# data_proV1_3.net
KiCad netlist of a schematic drawn in EAGLE
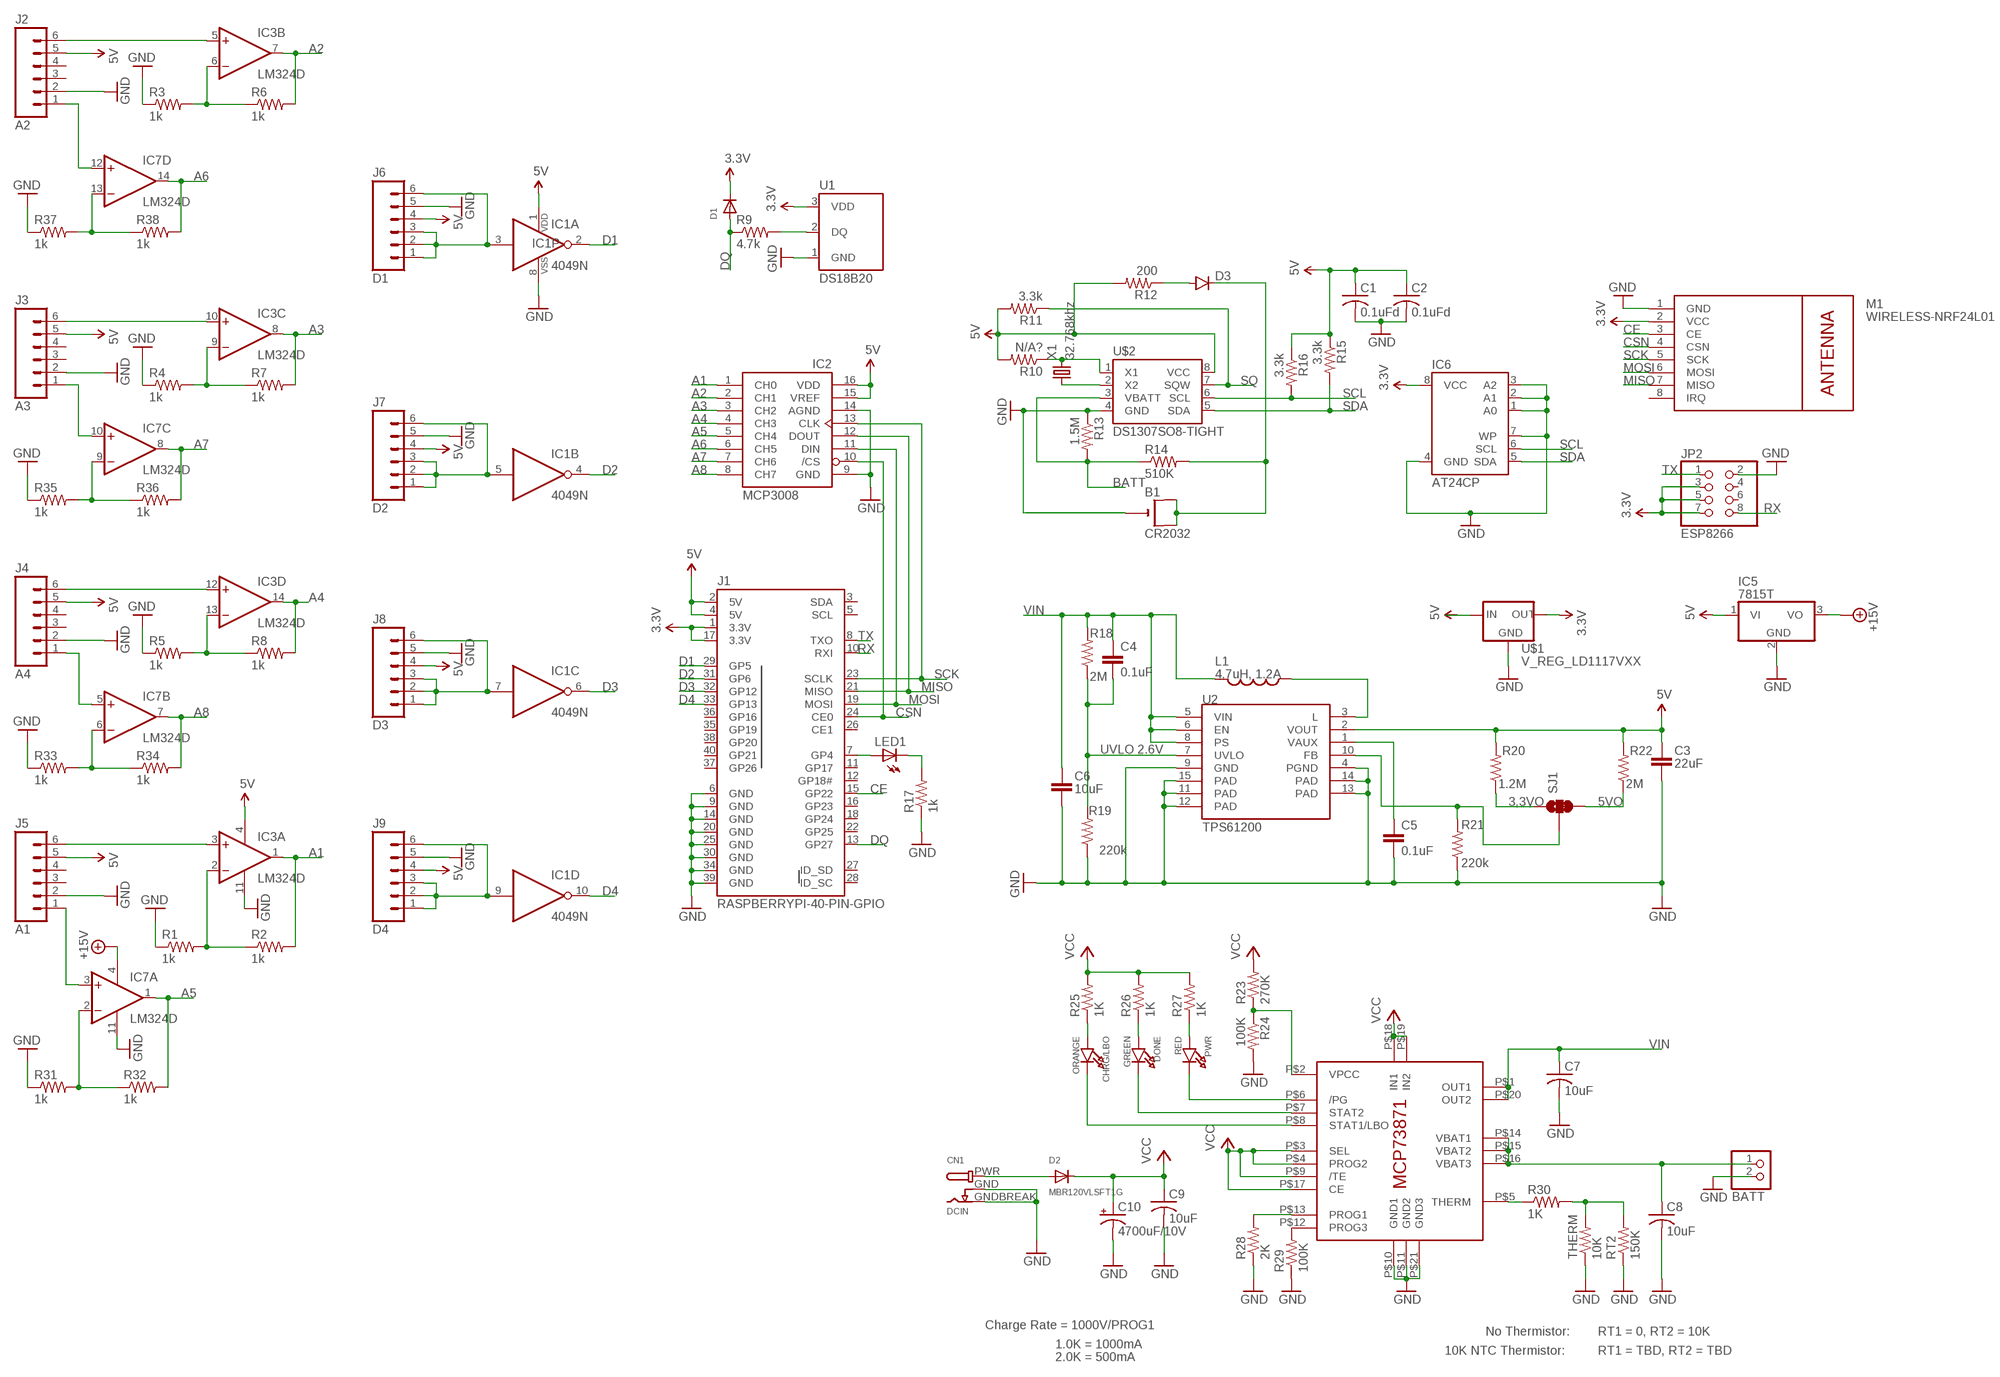
[diagram p0: schematic, sheet 1]

(export (version "E")
  (design (tool "Eeschema 10.0.6"))
  (components
    (comp (ref "B1")
      (value "CR2032")
      (footprint "eagle-import:CR2032-SMD")
      (libsource (lib "eagle-import") (part "CR2032SMT"))
    )
    (comp (ref "BATT")
      (value "JST_2PIN-SMT-RA")
      (footprint "eagle-import:JST-PH-2-SMT-RA")
      (libsource (lib "eagle-import") (part "JST_2PIN-SMT-RA"))
    )
    (comp (ref "C1")
      (value "0.1uFd")
      (footprint "eagle-import:C0805")
      (libsource (lib "eagle-import") (part "resistor_C-USC0805"))
    )
    (comp (ref "C2")
      (value "0.1uFd")
      (footprint "eagle-import:C0805")
      (libsource (lib "eagle-import") (part "resistor_C-USC0805"))
    )
    (comp (ref "C3")
      (value "22uF")
      (footprint "eagle-import:0805")
      (libsource (lib "eagle-import") (part "CAP0805"))
    )
    (comp (ref "C4")
      (value "0.1uF")
      (footprint "eagle-import:0603-CAP")
      (libsource (lib "eagle-import") (part "CAP0603-CAP"))
    )
    (comp (ref "C5")
      (value "0.1uF")
      (footprint "eagle-import:0603-CAP")
      (libsource (lib "eagle-import") (part "CAP0603-CAP"))
    )
    (comp (ref "C6")
      (value "10uF")
      (footprint "eagle-import:1206")
      (libsource (lib "eagle-import") (part "CAP1206"))
    )
    (comp (ref "C7")
      (value "10uF")
      (footprint "eagle-import:C0805K")
      (libsource (lib "eagle-import") (part "C-USC0805K"))
    )
    (comp (ref "C8")
      (value "10uF")
      (footprint "eagle-import:C0805K")
      (libsource (lib "eagle-import") (part "C-USC0805K"))
    )
    (comp (ref "C9")
      (value "10uF")
      (footprint "eagle-import:C0805K")
      (libsource (lib "eagle-import") (part "C-USC0805K"))
    )
    (comp (ref "C10")
      (value "4700uF/10V")
      (footprint "eagle-import:E5-13")
      (libsource (lib "eagle-import") (part "CPOL-USE5-13"))
    )
    (comp (ref "CHRG/LBO")
      (value "ORANGE")
      (footprint "eagle-import:CHIPLED_0805_NOOUTLINE")
      (libsource (lib "eagle-import") (part "LED0805_NOOUTLINE"))
    )
    (comp (ref "CN1")
      (value "DCIN")
      (footprint "eagle-import:DCJACK_2MM_SMT")
      (libsource (lib "eagle-import") (part "DCBARRELSMT"))
    )
    (comp (ref "D1")
      (value "DIODESOD-323F")
      (footprint "eagle-import:SOD-323F")
      (libsource (lib "eagle-import") (part "DIODESOD-323F"))
    )
    (comp (ref "D2")
      (value "MBR120VLSFT1G")
      (footprint "eagle-import:SOD-123")
      (libsource (lib "eagle-import") (part "microbuilder_DIODESOD-123"))
    )
    (comp (ref "D3")
      (value "DIODESMB")
      (footprint "eagle-import:SMB-DIODE")
      (libsource (lib "eagle-import") (part "DIODESMB"))
    )
    (comp (ref "DONE")
      (value "GREEN")
      (footprint "eagle-import:CHIPLED_0805_NOOUTLINE")
      (libsource (lib "eagle-import") (part "LED0805_NOOUTLINE"))
    )
    (comp (ref "IC1")
      (value "4049N")
      (footprint "eagle-import:DIL16")
      (libsource (lib "eagle-import") (part "4049N"))
    )
    (comp (ref "IC2")
      (value "MCP3008")
      (footprint "eagle-import:DIL16")
      (libsource (lib "eagle-import") (part "MCP3008"))
    )
    (comp (ref "IC3")
      (value "LM324D")
      (footprint "eagle-import:SO14")
      (libsource (lib "eagle-import") (part "LM324D"))
    )
    (comp (ref "IC4")
      (value "MCP73871")
      (footprint "eagle-import:QFN20_4MM")
      (libsource (lib "eagle-import") (part "MCP73871"))
    )
    (comp (ref "IC5")
      (value "7815T")
      (footprint "eagle-import:TO220H")
      (libsource (lib "eagle-import") (part "78T15"))
    )
    (comp (ref "IC6")
      (value "AT24CP")
      (footprint "eagle-import:DIL08")
      (fields (field (name "MPN") "AT24C1024BW-SH-B"))
      (libsource (lib "eagle-import") (part "AT24CP"))
    )
    (comp (ref "IC7")
      (value "LM324D")
      (footprint "eagle-import:SO14")
      (libsource (lib "eagle-import") (part "LM324D"))
    )
    (comp (ref "J1")
      (value "RASPBERRYPI-40-PIN-GPIO")
      (footprint "eagle-import:2X20-SHROUDED")
      (libsource (lib "eagle-import") (part "RASPBERRYPI-40-PIN-GPIO"))
    )
    (comp (ref "J2")
      (value "A2")
      (footprint "eagle-import:BTA")
      (libsource (lib "eagle-import") (part "M06VERNIER-ANALOG"))
    )
    (comp (ref "J3")
      (value "A3")
      (footprint "eagle-import:BTA")
      (libsource (lib "eagle-import") (part "M06VERNIER-ANALOG"))
    )
    (comp (ref "J4")
      (value "A4")
      (footprint "eagle-import:BTA")
      (libsource (lib "eagle-import") (part "M06VERNIER-ANALOG"))
    )
    (comp (ref "J5")
      (value "A1")
      (footprint "eagle-import:BTA")
      (libsource (lib "eagle-import") (part "M06VERNIER-ANALOG"))
    )
    (comp (ref "J6")
      (value "D1")
      (footprint "eagle-import:BTD")
      (libsource (lib "eagle-import") (part "M06VERNIER-DIGITAL"))
    )
    (comp (ref "J7")
      (value "D2")
      (footprint "eagle-import:BTD")
      (libsource (lib "eagle-import") (part "M06VERNIER-DIGITAL"))
    )
    (comp (ref "J8")
      (value "D3")
      (footprint "eagle-import:BTD")
      (libsource (lib "eagle-import") (part "M06VERNIER-DIGITAL"))
    )
    (comp (ref "J9")
      (value "D4")
      (footprint "eagle-import:BTD")
      (libsource (lib "eagle-import") (part "M06VERNIER-DIGITAL"))
    )
    (comp (ref "JP2")
      (value "ESP8266")
      (footprint "eagle-import:2X04")
      (libsource (lib "eagle-import") (part "PINHD-2X4"))
    )
    (comp (ref "L1")
      (value "4.7uH, 1.2A")
      (footprint "eagle-import:CDRH2D09")
      (libsource (lib "eagle-import") (part "INDUCTOR."))
    )
    (comp (ref "LED1")
      (value "LEDCHIP-LED0805")
      (footprint "eagle-import:CHIP-LED0805")
      (libsource (lib "eagle-import") (part "LEDCHIP-LED0805"))
    )
    (comp (ref "M1")
      (value "WIRELESS-NRF24L01")
      (footprint "eagle-import:WIRELESS-NRF24L01")
      (libsource (lib "eagle-import") (part "WIRELESS-NRF24L01"))
    )
    (comp (ref "PWR")
      (value "RED")
      (footprint "eagle-import:CHIPLED_0805_NOOUTLINE")
      (libsource (lib "eagle-import") (part "LED0805_NOOUTLINE"))
    )
    (comp (ref "R1")
      (value "1k")
      (footprint "eagle-import:R0805")
      (libsource (lib "eagle-import") (part "resistor_R-US_R0805"))
    )
    (comp (ref "R2")
      (value "1k")
      (footprint "eagle-import:R0805")
      (libsource (lib "eagle-import") (part "resistor_R-US_R0805"))
    )
    (comp (ref "R3")
      (value "1k")
      (footprint "eagle-import:R0805")
      (libsource (lib "eagle-import") (part "resistor_R-US_R0805"))
    )
    (comp (ref "R4")
      (value "1k")
      (footprint "eagle-import:R0805")
      (libsource (lib "eagle-import") (part "resistor_R-US_R0805"))
    )
    (comp (ref "R5")
      (value "1k")
      (footprint "eagle-import:R0805")
      (libsource (lib "eagle-import") (part "resistor_R-US_R0805"))
    )
    (comp (ref "R6")
      (value "1k")
      (footprint "eagle-import:R0805")
      (libsource (lib "eagle-import") (part "resistor_R-US_R0805"))
    )
    (comp (ref "R7")
      (value "1k")
      (footprint "eagle-import:R0805")
      (libsource (lib "eagle-import") (part "resistor_R-US_R0805"))
    )
    (comp (ref "R8")
      (value "1k")
      (footprint "eagle-import:R0805")
      (libsource (lib "eagle-import") (part "resistor_R-US_R0805"))
    )
    (comp (ref "R9")
      (value "4.7k")
      (footprint "eagle-import:R0805")
      (libsource (lib "eagle-import") (part "resistor_R-US_R0805"))
    )
    (comp (ref "R10")
      (value "N/A?")
      (footprint "eagle-import:R0805")
      (libsource (lib "eagle-import") (part "R-US_R0805"))
    )
    (comp (ref "R11")
      (value "3.3k")
      (footprint "eagle-import:R0805")
      (libsource (lib "eagle-import") (part "R-US_R0805"))
    )
    (comp (ref "R12")
      (value "200")
      (footprint "eagle-import:R0805")
      (libsource (lib "eagle-import") (part "R-US_R0805"))
    )
    (comp (ref "R13")
      (value "1.5M")
      (footprint "eagle-import:R0805")
      (libsource (lib "eagle-import") (part "R-US_R0805"))
    )
    (comp (ref "R14")
      (value "510K")
      (footprint "eagle-import:R0805")
      (libsource (lib "eagle-import") (part "R-US_R0805"))
    )
    (comp (ref "R15")
      (value "3.3k")
      (footprint "eagle-import:R0805")
      (libsource (lib "eagle-import") (part "R-US_R0805"))
    )
    (comp (ref "R16")
      (value "3.3k")
      (footprint "eagle-import:R0805")
      (libsource (lib "eagle-import") (part "R-US_R0805"))
    )
    (comp (ref "R17")
      (value "1k")
      (footprint "eagle-import:R0805")
      (libsource (lib "eagle-import") (part "R-US_R0805"))
    )
    (comp (ref "R18")
      (value "2M")
      (footprint "eagle-import:0603-RES")
      (libsource (lib "eagle-import") (part "RESISTOR0603-RES"))
    )
    (comp (ref "R19")
      (value "220k")
      (footprint "eagle-import:0603-RES")
      (libsource (lib "eagle-import") (part "RESISTOR0603-RES"))
    )
    (comp (ref "R20")
      (value "1.2M")
      (footprint "eagle-import:0603-RES")
      (libsource (lib "eagle-import") (part "RESISTOR0603-RES"))
    )
    (comp (ref "R21")
      (value "220k")
      (footprint "eagle-import:0603-RES")
      (libsource (lib "eagle-import") (part "RESISTOR0603-RES"))
    )
    (comp (ref "R22")
      (value "2M")
      (footprint "eagle-import:0603-RES")
      (libsource (lib "eagle-import") (part "RESISTOR0603-RES"))
    )
    (comp (ref "R23")
      (value "270K")
      (footprint "eagle-import:R0805")
      (libsource (lib "eagle-import") (part "R-US_R0805"))
    )
    (comp (ref "R24")
      (value "100K")
      (footprint "eagle-import:R0805")
      (libsource (lib "eagle-import") (part "R-US_R0805"))
    )
    (comp (ref "R25")
      (value "1K")
      (footprint "eagle-import:R0805")
      (libsource (lib "eagle-import") (part "R-US_R0805"))
    )
    (comp (ref "R26")
      (value "1K")
      (footprint "eagle-import:R0805")
      (libsource (lib "eagle-import") (part "R-US_R0805"))
    )
    (comp (ref "R27")
      (value "1K")
      (footprint "eagle-import:R0805")
      (libsource (lib "eagle-import") (part "R-US_R0805"))
    )
    (comp (ref "R28")
      (value "2K")
      (footprint "eagle-import:0805-THM")
      (libsource (lib "eagle-import") (part "R-US_FLIPFLOP"))
    )
    (comp (ref "R29")
      (value "100K")
      (footprint "eagle-import:R0805")
      (libsource (lib "eagle-import") (part "R-US_R0805"))
    )
    (comp (ref "R30")
      (value "1K")
      (footprint "eagle-import:M0805")
      (libsource (lib "eagle-import") (part "R-US_M0805"))
    )
    (comp (ref "R31")
      (value "1k")
      (footprint "eagle-import:R0805")
      (libsource (lib "eagle-import") (part "resistor_R-US_R0805"))
    )
    (comp (ref "R32")
      (value "1k")
      (footprint "eagle-import:R0805")
      (libsource (lib "eagle-import") (part "resistor_R-US_R0805"))
    )
    (comp (ref "R33")
      (value "1k")
      (footprint "eagle-import:R0805")
      (libsource (lib "eagle-import") (part "resistor_R-US_R0805"))
    )
    (comp (ref "R34")
      (value "1k")
      (footprint "eagle-import:R0805")
      (libsource (lib "eagle-import") (part "resistor_R-US_R0805"))
    )
    (comp (ref "R35")
      (value "1k")
      (footprint "eagle-import:R0805")
      (libsource (lib "eagle-import") (part "resistor_R-US_R0805"))
    )
    (comp (ref "R36")
      (value "1k")
      (footprint "eagle-import:R0805")
      (libsource (lib "eagle-import") (part "resistor_R-US_R0805"))
    )
    (comp (ref "R37")
      (value "1k")
      (footprint "eagle-import:R0805")
      (libsource (lib "eagle-import") (part "resistor_R-US_R0805"))
    )
    (comp (ref "R38")
      (value "1k")
      (footprint "eagle-import:R0805")
      (libsource (lib "eagle-import") (part "resistor_R-US_R0805"))
    )
    (comp (ref "RT2")
      (value "150K")
      (footprint "eagle-import:M0805")
      (libsource (lib "eagle-import") (part "R-US_M0805"))
    )
    (comp (ref "SJ1")
      (value "SOLDERJUMPER_2WAYPASTE2&3")
      (footprint "eagle-import:SJ_3_PASTE2&3")
      (libsource (lib "eagle-import") (part "SOLDERJUMPER_2WAYPASTE2&3"))
    )
    (comp (ref "THERM")
      (value "10K")
      (footprint "eagle-import:0805-THM")
      (libsource (lib "eagle-import") (part "R-US_FLIPFLOP"))
    )
    (comp (ref "U$1")
      (value "V_REG_LD1117VXX")
      (footprint "eagle-import:78XXL")
      (libsource (lib "eagle-import") (part "V_REG_LD1117VXX"))
    )
    (comp (ref "U$2")
      (value "DS1307SO8-TIGHT")
      (footprint "eagle-import:SO08-TIGHT")
      (libsource (lib "eagle-import") (part "DS1307SO8-TIGHT"))
    )
    (comp (ref "U1")
      (value "DS18B20")
      (footprint "eagle-import:TO-92-AMMO")
      (libsource (lib "eagle-import") (part "DS18B20"))
    )
    (comp (ref "U2")
      (value "TPS61200")
      (footprint "eagle-import:QFN-10_PAD")
      (libsource (lib "eagle-import") (part "TPS61200"))
    )
    (comp (ref "X1")
      (value "32.768khz")
      (footprint "eagle-import:TC38H")
      (libsource (lib "eagle-import") (part "CRYSTALTC38H"))
    )
  )
  (nets
    (net (code "1") (name "+15V") (class "Default")
      (node (ref "IC5") (pin "3") (pinfunction "VO_3") (pintype "passive"))
      (node (ref "IC7") (pin "4") (pinfunction "V+_4") (pintype "power_in"))
    )
    (net (code "2") (name "/3.3VO") (class "Default")
      (node (ref "R20") (pin "1") (pinfunction "1_1") (pintype "passive"))
      (node (ref "SJ1") (pin "1") (pinfunction "1_1") (pintype "passive"))
    )
    (net (code "3") (name "/5VO") (class "Default")
      (node (ref "R22") (pin "1") (pinfunction "1_1") (pintype "passive"))
      (node (ref "SJ1") (pin "3") (pinfunction "3_3") (pintype "passive"))
    )
    (net (code "4") (name "/A1") (class "Default")
      (node (ref "IC2") (pin "1") (pinfunction "CH0_1") (pintype "input"))
      (node (ref "IC3") (pin "1") (pinfunction "OUT_1") (pintype "output"))
      (node (ref "R2") (pin "2") (pinfunction "2_2") (pintype "passive"))
    )
    (net (code "5") (name "/A2") (class "Default")
      (node (ref "IC2") (pin "2") (pinfunction "CH1_2") (pintype "input"))
      (node (ref "IC3") (pin "7") (pinfunction "OUT_7") (pintype "output"))
      (node (ref "R6") (pin "2") (pinfunction "2_2") (pintype "passive"))
    )
    (net (code "6") (name "/A3") (class "Default")
      (node (ref "IC2") (pin "3") (pinfunction "CH2_3") (pintype "input"))
      (node (ref "IC3") (pin "8") (pinfunction "OUT_8") (pintype "output"))
      (node (ref "R7") (pin "2") (pinfunction "2_2") (pintype "passive"))
    )
    (net (code "7") (name "/A4") (class "Default")
      (node (ref "IC2") (pin "4") (pinfunction "CH3_4") (pintype "input"))
      (node (ref "IC3") (pin "14") (pinfunction "OUT_14") (pintype "output"))
      (node (ref "R8") (pin "2") (pinfunction "2_2") (pintype "passive"))
    )
    (net (code "8") (name "/A5") (class "Default")
      (node (ref "IC2") (pin "5") (pinfunction "CH4_5") (pintype "input"))
      (node (ref "IC7") (pin "1") (pinfunction "OUT_1") (pintype "output"))
      (node (ref "R32") (pin "2") (pinfunction "2_2") (pintype "passive"))
    )
    (net (code "9") (name "/A6") (class "Default")
      (node (ref "IC2") (pin "6") (pinfunction "CH5_6") (pintype "input"))
      (node (ref "IC7") (pin "14") (pinfunction "OUT_14") (pintype "output"))
      (node (ref "R38") (pin "2") (pinfunction "2_2") (pintype "passive"))
    )
    (net (code "10") (name "/A7") (class "Default")
      (node (ref "IC2") (pin "7") (pinfunction "CH6_7") (pintype "input"))
      (node (ref "IC7") (pin "8") (pinfunction "OUT_8") (pintype "output"))
      (node (ref "R36") (pin "2") (pinfunction "2_2") (pintype "passive"))
    )
    (net (code "11") (name "/A8") (class "Default")
      (node (ref "IC2") (pin "8") (pinfunction "CH7_8") (pintype "input"))
      (node (ref "IC7") (pin "7") (pinfunction "OUT_7") (pintype "output"))
      (node (ref "R34") (pin "2") (pinfunction "2_2") (pintype "passive"))
    )
    (net (code "12") (name "/BATT") (class "Default")
      (node (ref "R13") (pin "2") (pinfunction "2_2") (pintype "passive"))
      (node (ref "R14") (pin "1") (pinfunction "1_1") (pintype "passive"))
      (node (ref "U$2") (pin "3") (pinfunction "VBATT_3") (pintype "bidirectional"))
    )
    (net (code "13") (name "/CE") (class "Default")
      (node (ref "J1") (pin "15") (pinfunction "GP22_15") (pintype "bidirectional"))
      (node (ref "M1") (pin "3") (pinfunction "CE_3") (pintype "bidirectional"))
    )
    (net (code "14") (name "/CSN") (class "Default")
      (node (ref "IC2") (pin "10") (pinfunction "/CS_10") (pintype "input"))
      (node (ref "J1") (pin "24") (pinfunction "CE0_24") (pintype "output"))
      (node (ref "M1") (pin "4") (pinfunction "CSN_4") (pintype "bidirectional"))
    )
    (net (code "15") (name "/D1") (class "Default")
      (node (ref "IC1") (pin "2") (pinfunction "O_2") (pintype "output"))
      (node (ref "J1") (pin "29") (pinfunction "GP5_29") (pintype "bidirectional"))
    )
    (net (code "16") (name "/D2") (class "Default")
      (node (ref "IC1") (pin "4") (pinfunction "O_4") (pintype "output"))
      (node (ref "J1") (pin "31") (pinfunction "GP6_31") (pintype "bidirectional"))
    )
    (net (code "17") (name "/D3") (class "Default")
      (node (ref "IC1") (pin "6") (pinfunction "O_6") (pintype "output"))
      (node (ref "J1") (pin "32") (pinfunction "GP12_32") (pintype "bidirectional"))
    )
    (net (code "18") (name "/D4") (class "Default")
      (node (ref "IC1") (pin "10") (pinfunction "O_10") (pintype "output"))
      (node (ref "J1") (pin "33") (pinfunction "GP13_33") (pintype "bidirectional"))
    )
    (net (code "19") (name "/DQ") (class "Default")
      (node (ref "D1") (pin "A") (pinfunction "A_A") (pintype "passive"))
      (node (ref "J1") (pin "13") (pinfunction "GP27_13") (pintype "bidirectional"))
      (node (ref "R9") (pin "1") (pinfunction "1_1") (pintype "passive"))
    )
    (net (code "20") (name "/MISO") (class "Default")
      (node (ref "IC2") (pin "12") (pinfunction "DOUT_12") (pintype "output"))
      (node (ref "J1") (pin "21") (pinfunction "MISO_21") (pintype "input"))
      (node (ref "M1") (pin "7") (pinfunction "MISO_7") (pintype "bidirectional"))
    )
    (net (code "21") (name "/MOSI") (class "Default")
      (node (ref "IC2") (pin "11") (pinfunction "DIN_11") (pintype "input"))
      (node (ref "J1") (pin "19") (pinfunction "MOSI_19") (pintype "output"))
      (node (ref "M1") (pin "6") (pinfunction "MOSI_6") (pintype "bidirectional"))
    )
    (net (code "22") (name "/RX") (class "Default")
      (node (ref "J1") (pin "10") (pinfunction "RXI_10") (pintype "input"))
      (node (ref "JP2") (pin "8") (pinfunction "8_8") (pintype "passive"))
    )
    (net (code "23") (name "/SCK") (class "Default")
      (node (ref "IC2") (pin "13") (pinfunction "CLK_13") (pintype "input"))
      (node (ref "J1") (pin "23") (pinfunction "SCLK_23") (pintype "output"))
      (node (ref "M1") (pin "5") (pinfunction "SCK_5") (pintype "bidirectional"))
    )
    (net (code "24") (name "/SCL") (class "Default")
      (node (ref "IC6") (pin "6") (pinfunction "SCL_6") (pintype "bidirectional"))
      (node (ref "R16") (pin "2") (pinfunction "2_2") (pintype "passive"))
      (node (ref "U$2") (pin "6") (pinfunction "SCL_6") (pintype "bidirectional"))
    )
    (net (code "25") (name "/SDA") (class "Default")
      (node (ref "IC6") (pin "5") (pinfunction "SDA_5") (pintype "bidirectional"))
      (node (ref "R15") (pin "2") (pinfunction "2_2") (pintype "passive"))
      (node (ref "U$2") (pin "5") (pinfunction "SDA_5") (pintype "bidirectional"))
    )
    (net (code "26") (name "/SQ") (class "Default")
      (node (ref "R11") (pin "1") (pinfunction "1_1") (pintype "passive"))
      (node (ref "U$2") (pin "7") (pinfunction "SQW_7") (pintype "bidirectional"))
    )
    (net (code "27") (name "/TX") (class "Default")
      (node (ref "J1") (pin "8") (pinfunction "TXO_8") (pintype "output"))
      (node (ref "JP2") (pin "1") (pinfunction "1_1") (pintype "passive"))
    )
    (net (code "28") (name "/VIN") (class "Default")
      (node (ref "C4") (pin "1") (pinfunction "1_1") (pintype "passive"))
      (node (ref "C6") (pin "1") (pinfunction "1_1") (pintype "passive"))
      (node (ref "C7") (pin "1") (pinfunction "1_1") (pintype "passive"))
      (node (ref "IC4") (pin "P$1") (pinfunction "OUT1_P$1") (pintype "output"))
      (node (ref "IC4") (pin "P$20") (pinfunction "OUT2_P$20") (pintype "output"))
      (node (ref "L1") (pin "P$2") (pinfunction "2_P$2") (pintype "passive"))
      (node (ref "R18") (pin "2") (pinfunction "2_2") (pintype "passive"))
      (node (ref "U2") (pin "5") (pinfunction "VIN_5") (pintype "power_in"))
      (node (ref "U2") (pin "6") (pinfunction "EN_6") (pintype "input"))
      (node (ref "U2") (pin "8") (pinfunction "PS_8") (pintype "input"))
    )
    (net (code "29") (name "3.3V") (class "Default")
      (node (ref "D1") (pin "C") (pinfunction "C_C") (pintype "passive"))
      (node (ref "IC6") (pin "8") (pinfunction "VCC_8") (pintype "power_in"))
      (node (ref "J1") (pin "1") (pinfunction "3.3V_1") (pintype "power_in"))
      (node (ref "J1") (pin "17") (pinfunction "3.3V_17") (pintype "power_in"))
      (node (ref "JP2") (pin "3") (pinfunction "3_3") (pintype "passive"))
      (node (ref "JP2") (pin "5") (pinfunction "5_5") (pintype "passive"))
      (node (ref "JP2") (pin "7") (pinfunction "7_7") (pintype "passive"))
      (node (ref "M1") (pin "2") (pinfunction "VCC_2") (pintype "power_in"))
      (node (ref "U$1") (pin "GND") (pinfunction "OUT_GND") (pintype "passive"))
      (node (ref "U1") (pin "3") (pinfunction "VDD_3") (pintype "power_in"))
    )
    (net (code "30") (name "5V") (class "Default")
      (node (ref "C1") (pin "1") (pinfunction "1_1") (pintype "passive"))
      (node (ref "C2") (pin "1") (pinfunction "1_1") (pintype "passive"))
      (node (ref "C3") (pin "1") (pinfunction "1_1") (pintype "passive"))
      (node (ref "IC1") (pin "1") (pinfunction "VDD_1") (pintype "power_in"))
      (node (ref "IC2") (pin "15") (pinfunction "VREF_15") (pintype "input"))
      (node (ref "IC2") (pin "16") (pinfunction "VDD_16") (pintype "power_in"))
      (node (ref "IC3") (pin "4") (pinfunction "V+_4") (pintype "power_in"))
      (node (ref "IC5") (pin "1") (pinfunction "VI_1") (pintype "input"))
      (node (ref "J1") (pin "2") (pinfunction "5V_2") (pintype "power_in"))
      (node (ref "J1") (pin "4") (pinfunction "5V_4") (pintype "power_in"))
      (node (ref "J2") (pin "5") (pinfunction "5_5") (pintype "passive"))
      (node (ref "J3") (pin "5") (pinfunction "5_5") (pintype "passive"))
      (node (ref "J4") (pin "5") (pinfunction "5_5") (pintype "passive"))
      (node (ref "J5") (pin "5") (pinfunction "5_5") (pintype "passive"))
      (node (ref "J6") (pin "4") (pinfunction "4_4") (pintype "passive"))
      (node (ref "J7") (pin "4") (pinfunction "4_4") (pintype "passive"))
      (node (ref "J8") (pin "4") (pinfunction "4_4") (pintype "passive"))
      (node (ref "J9") (pin "4") (pinfunction "4_4") (pintype "passive"))
      (node (ref "R10") (pin "2") (pinfunction "2_2") (pintype "passive"))
      (node (ref "R11") (pin "2") (pinfunction "2_2") (pintype "passive"))
      (node (ref "R12") (pin "2") (pinfunction "2_2") (pintype "passive"))
      (node (ref "R15") (pin "1") (pinfunction "1_1") (pintype "passive"))
      (node (ref "R16") (pin "1") (pinfunction "1_1") (pintype "passive"))
      (node (ref "R20") (pin "2") (pinfunction "2_2") (pintype "passive"))
      (node (ref "R22") (pin "2") (pinfunction "2_2") (pintype "passive"))
      (node (ref "U$1") (pin "OUT") (pinfunction "IN_OUT") (pintype "input"))
      (node (ref "U$2") (pin "8") (pinfunction "VCC_8") (pintype "bidirectional"))
      (node (ref "U2") (pin "2") (pinfunction "VOUT_2") (pintype "passive"))
    )
    (net (code "31") (name "GND") (class "Default")
      (node (ref "B1") (pin "-") (pinfunction "-_-") (pintype "passive"))
      (node (ref "BATT") (pin "2") (pinfunction "1_2") (pintype "passive"))
      (node (ref "C1") (pin "2") (pinfunction "2_2") (pintype "passive"))
      (node (ref "C10") (pin "-") (pinfunction "-_-") (pintype "passive"))
      (node (ref "C2") (pin "2") (pinfunction "2_2") (pintype "passive"))
      (node (ref "C3") (pin "2") (pinfunction "2_2") (pintype "passive"))
      (node (ref "C5") (pin "2") (pinfunction "2_2") (pintype "passive"))
      (node (ref "C6") (pin "2") (pinfunction "2_2") (pintype "passive"))
      (node (ref "C7") (pin "2") (pinfunction "2_2") (pintype "passive"))
      (node (ref "C8") (pin "2") (pinfunction "2_2") (pintype "passive"))
      (node (ref "C9") (pin "2") (pinfunction "2_2") (pintype "passive"))
      (node (ref "CN1") (pin "GND") (pinfunction "GNDBREAK_GND") (pintype "power_in"))
      (node (ref "CN1") (pin "GNDBREAK") (pinfunction "GND_GNDBREAK") (pintype "power_in"))
      (node (ref "IC1") (pin "8") (pinfunction "VSS_8") (pintype "power_in"))
      (node (ref "IC2") (pin "14") (pinfunction "AGND_14") (pintype "power_in"))
      (node (ref "IC2") (pin "9") (pinfunction "GND_9") (pintype "power_in"))
      (node (ref "IC3") (pin "11") (pinfunction "V-_11") (pintype "power_in"))
      (node (ref "IC4") (pin "P$10") (pinfunction "GND1_P$10") (pintype "power_in"))
      (node (ref "IC4") (pin "P$11") (pinfunction "GND2_P$11") (pintype "power_in"))
      (node (ref "IC4") (pin "P$21") (pinfunction "GND3_P$21") (pintype "power_in"))
      (node (ref "IC5") (pin "2") (pinfunction "GND_2") (pintype "passive"))
      (node (ref "IC6") (pin "1") (pinfunction "A0_1") (pintype "input"))
      (node (ref "IC6") (pin "2") (pinfunction "A1_2") (pintype "input"))
      (node (ref "IC6") (pin "3") (pinfunction "A2_3") (pintype "input"))
      (node (ref "IC6") (pin "4") (pinfunction "GND_4") (pintype "power_in"))
      (node (ref "IC6") (pin "7") (pinfunction "WP_7") (pintype "input"))
      (node (ref "IC7") (pin "11") (pinfunction "V-_11") (pintype "power_in"))
      (node (ref "J1") (pin "14") (pinfunction "GND_14") (pintype "power_in"))
      (node (ref "J1") (pin "20") (pinfunction "GND_20") (pintype "power_in"))
      (node (ref "J1") (pin "25") (pinfunction "GND_25") (pintype "power_in"))
      (node (ref "J1") (pin "30") (pinfunction "GND_30") (pintype "power_in"))
      (node (ref "J1") (pin "34") (pinfunction "GND_34") (pintype "power_in"))
      (node (ref "J1") (pin "39") (pinfunction "GND_39") (pintype "power_in"))
      (node (ref "J1") (pin "6") (pinfunction "GND_6") (pintype "power_in"))
      (node (ref "J1") (pin "9") (pinfunction "GND_9") (pintype "power_in"))
      (node (ref "J2") (pin "2") (pinfunction "2_2") (pintype "passive"))
      (node (ref "J3") (pin "2") (pinfunction "2_2") (pintype "passive"))
      (node (ref "J4") (pin "2") (pinfunction "2_2") (pintype "passive"))
      (node (ref "J5") (pin "2") (pinfunction "2_2") (pintype "passive"))
      (node (ref "J6") (pin "5") (pinfunction "5_5") (pintype "passive"))
      (node (ref "J7") (pin "5") (pinfunction "5_5") (pintype "passive"))
      (node (ref "J8") (pin "5") (pinfunction "5_5") (pintype "passive"))
      (node (ref "J9") (pin "5") (pinfunction "5_5") (pintype "passive"))
      (node (ref "JP2") (pin "2") (pinfunction "2_2") (pintype "passive"))
      (node (ref "M1") (pin "1") (pinfunction "GND_1") (pintype "power_in"))
      (node (ref "R1") (pin "1") (pinfunction "1_1") (pintype "passive"))
      (node (ref "R13") (pin "1") (pinfunction "1_1") (pintype "passive"))
      (node (ref "R17") (pin "1") (pinfunction "1_1") (pintype "passive"))
      (node (ref "R19") (pin "1") (pinfunction "1_1") (pintype "passive"))
      (node (ref "R21") (pin "1") (pinfunction "1_1") (pintype "passive"))
      (node (ref "R24") (pin "2") (pinfunction "2_2") (pintype "passive"))
      (node (ref "R28") (pin "1") (pinfunction "1_1") (pintype "passive"))
      (node (ref "R29") (pin "1") (pinfunction "1_1") (pintype "passive"))
      (node (ref "R3") (pin "1") (pinfunction "1_1") (pintype "passive"))
      (node (ref "R31") (pin "1") (pinfunction "1_1") (pintype "passive"))
      (node (ref "R33") (pin "1") (pinfunction "1_1") (pintype "passive"))
      (node (ref "R35") (pin "1") (pinfunction "1_1") (pintype "passive"))
      (node (ref "R37") (pin "1") (pinfunction "1_1") (pintype "passive"))
      (node (ref "R4") (pin "1") (pinfunction "1_1") (pintype "passive"))
      (node (ref "R5") (pin "1") (pinfunction "1_1") (pintype "passive"))
      (node (ref "RT2") (pin "1") (pinfunction "1_1") (pintype "passive"))
      (node (ref "THERM") (pin "1") (pinfunction "1_1") (pintype "passive"))
      (node (ref "U$1") (pin "IN") (pinfunction "GND_IN") (pintype "input"))
      (node (ref "U$2") (pin "4") (pinfunction "GND_4") (pintype "bidirectional"))
      (node (ref "U1") (pin "1") (pinfunction "GND_1") (pintype "power_in"))
      (node (ref "U2") (pin "11") (pinfunction "PAD_11") (pintype "power_in"))
      (node (ref "U2") (pin "12") (pinfunction "PAD_12") (pintype "power_in"))
      (node (ref "U2") (pin "13") (pinfunction "PAD_13") (pintype "power_in"))
      (node (ref "U2") (pin "14") (pinfunction "PAD_14") (pintype "power_in"))
      (node (ref "U2") (pin "15") (pinfunction "PAD_15") (pintype "power_in"))
      (node (ref "U2") (pin "4") (pinfunction "PGND_4") (pintype "power_in"))
      (node (ref "U2") (pin "9") (pinfunction "GND_9") (pintype "power_in"))
    )
    (net (code "32") (name "Net-(B1-+)") (class "Default")
      (node (ref "B1") (pin "+$1") (pinfunction "+_+$1") (pintype "passive"))
      (node (ref "B1") (pin "+$2") (pinfunction "+1_+$2") (pintype "passive"))
      (node (ref "D3") (pin "C") (pinfunction "C_C") (pintype "passive"))
      (node (ref "R14") (pin "2") (pinfunction "2_2") (pintype "passive"))
    )
    (net (code "33") (name "Net-(BATT-2)") (class "Default")
      (node (ref "BATT") (pin "1") (pinfunction "2_1") (pintype "passive"))
      (node (ref "C8") (pin "1") (pinfunction "1_1") (pintype "passive"))
      (node (ref "IC4") (pin "P$14") (pinfunction "VBAT1_P$14") (pintype "output"))
      (node (ref "IC4") (pin "P$15") (pinfunction "VBAT2_P$15") (pintype "output"))
      (node (ref "IC4") (pin "P$16") (pinfunction "VBAT3_P$16") (pintype "output"))
    )
    (net (code "34") (name "Net-(CHRG/LBO-PadA)") (class "Default")
      (node (ref "CHRG/LBO") (pin "A") (pinfunction "A_A") (pintype "passive"))
      (node (ref "R25") (pin "1") (pinfunction "1_1") (pintype "passive"))
    )
    (net (code "35") (name "Net-(CN1-PadPWR)") (class "Default")
      (node (ref "CN1") (pin "PWR") (pinfunction "PWR_PWR") (pintype "power_in"))
      (node (ref "D2") (pin "A") (pinfunction "A_A") (pintype "passive"))
    )
    (net (code "36") (name "Net-(D3-PadA)") (class "Default")
      (node (ref "D3") (pin "A") (pinfunction "A_A") (pintype "passive"))
      (node (ref "R12") (pin "1") (pinfunction "1_1") (pintype "passive"))
    )
    (net (code "37") (name "Net-(DONE-PadA)") (class "Default")
      (node (ref "DONE") (pin "A") (pinfunction "A_A") (pintype "passive"))
      (node (ref "R26") (pin "1") (pinfunction "1_1") (pintype "passive"))
    )
    (net (code "38") (name "Net-(IC1A-I)") (class "Default")
      (node (ref "IC1") (pin "3") (pinfunction "I_3") (pintype "input"))
      (node (ref "J6") (pin "1") (pinfunction "1_1") (pintype "passive"))
      (node (ref "J6") (pin "2") (pinfunction "2_2") (pintype "passive"))
      (node (ref "J6") (pin "3") (pinfunction "3_3") (pintype "passive"))
      (node (ref "J6") (pin "6") (pinfunction "6_6") (pintype "passive"))
    )
    (net (code "39") (name "Net-(IC1B-I)") (class "Default")
      (node (ref "IC1") (pin "5") (pinfunction "I_5") (pintype "input"))
      (node (ref "J7") (pin "1") (pinfunction "1_1") (pintype "passive"))
      (node (ref "J7") (pin "2") (pinfunction "2_2") (pintype "passive"))
      (node (ref "J7") (pin "3") (pinfunction "3_3") (pintype "passive"))
      (node (ref "J7") (pin "6") (pinfunction "6_6") (pintype "passive"))
    )
    (net (code "40") (name "Net-(IC1C-I)") (class "Default")
      (node (ref "IC1") (pin "7") (pinfunction "I_7") (pintype "input"))
      (node (ref "J8") (pin "1") (pinfunction "1_1") (pintype "passive"))
      (node (ref "J8") (pin "2") (pinfunction "2_2") (pintype "passive"))
      (node (ref "J8") (pin "3") (pinfunction "3_3") (pintype "passive"))
      (node (ref "J8") (pin "6") (pinfunction "6_6") (pintype "passive"))
    )
    (net (code "41") (name "Net-(IC1D-I)") (class "Default")
      (node (ref "IC1") (pin "9") (pinfunction "I_9") (pintype "input"))
      (node (ref "J9") (pin "1") (pinfunction "1_1") (pintype "passive"))
      (node (ref "J9") (pin "2") (pinfunction "2_2") (pintype "passive"))
      (node (ref "J9") (pin "3") (pinfunction "3_3") (pintype "passive"))
      (node (ref "J9") (pin "6") (pinfunction "6_6") (pintype "passive"))
    )
    (net (code "42") (name "Net-(IC3A-+IN)") (class "Default")
      (node (ref "IC3") (pin "3") (pinfunction "+IN_3") (pintype "input"))
      (node (ref "J5") (pin "6") (pinfunction "6_6") (pintype "passive"))
    )
    (net (code "43") (name "Net-(IC3A--IN)") (class "Default")
      (node (ref "IC3") (pin "2") (pinfunction "-IN_2") (pintype "input"))
      (node (ref "R1") (pin "2") (pinfunction "2_2") (pintype "passive"))
      (node (ref "R2") (pin "1") (pinfunction "1_1") (pintype "passive"))
    )
    (net (code "44") (name "Net-(IC3B-+IN)") (class "Default")
      (node (ref "IC3") (pin "5") (pinfunction "+IN_5") (pintype "input"))
      (node (ref "J2") (pin "6") (pinfunction "6_6") (pintype "passive"))
    )
    (net (code "45") (name "Net-(IC3B--IN)") (class "Default")
      (node (ref "IC3") (pin "6") (pinfunction "-IN_6") (pintype "input"))
      (node (ref "R3") (pin "2") (pinfunction "2_2") (pintype "passive"))
      (node (ref "R6") (pin "1") (pinfunction "1_1") (pintype "passive"))
    )
    (net (code "46") (name "Net-(IC3C-+IN)") (class "Default")
      (node (ref "IC3") (pin "10") (pinfunction "+IN_10") (pintype "input"))
      (node (ref "J3") (pin "6") (pinfunction "6_6") (pintype "passive"))
    )
    (net (code "47") (name "Net-(IC3C--IN)") (class "Default")
      (node (ref "IC3") (pin "9") (pinfunction "-IN_9") (pintype "input"))
      (node (ref "R4") (pin "2") (pinfunction "2_2") (pintype "passive"))
      (node (ref "R7") (pin "1") (pinfunction "1_1") (pintype "passive"))
    )
    (net (code "48") (name "Net-(IC3D-+IN)") (class "Default")
      (node (ref "IC3") (pin "12") (pinfunction "+IN_12") (pintype "input"))
      (node (ref "J4") (pin "6") (pinfunction "6_6") (pintype "passive"))
    )
    (net (code "49") (name "Net-(IC3D--IN)") (class "Default")
      (node (ref "IC3") (pin "13") (pinfunction "-IN_13") (pintype "input"))
      (node (ref "R5") (pin "2") (pinfunction "2_2") (pintype "passive"))
      (node (ref "R8") (pin "1") (pinfunction "1_1") (pintype "passive"))
    )
    (net (code "50") (name "Net-(IC4-PROG1)") (class "Default")
      (node (ref "IC4") (pin "P$13") (pinfunction "PROG1_P$13") (pintype "input"))
      (node (ref "R28") (pin "2") (pinfunction "2_2") (pintype "passive"))
    )
    (net (code "51") (name "Net-(IC4-PROG3)") (class "Default")
      (node (ref "IC4") (pin "P$12") (pinfunction "PROG3_P$12") (pintype "input"))
      (node (ref "R29") (pin "2") (pinfunction "2_2") (pintype "passive"))
    )
    (net (code "52") (name "Net-(IC4-STAT1{slash}LBO)") (class "Default")
      (node (ref "CHRG/LBO") (pin "C") (pinfunction "C_C") (pintype "passive"))
      (node (ref "IC4") (pin "P$8") (pinfunction "STAT1/LBO_P$8") (pintype "output"))
    )
    (net (code "53") (name "Net-(IC4-STAT2)") (class "Default")
      (node (ref "DONE") (pin "C") (pinfunction "C_C") (pintype "passive"))
      (node (ref "IC4") (pin "P$7") (pinfunction "STAT2_P$7") (pintype "output"))
    )
    (net (code "54") (name "Net-(IC4-THERM)") (class "Default")
      (node (ref "IC4") (pin "P$5") (pinfunction "THERM_P$5") (pintype "input"))
      (node (ref "R30") (pin "1") (pinfunction "1_1") (pintype "passive"))
    )
    (net (code "55") (name "Net-(IC4-VPCC)") (class "Default")
      (node (ref "IC4") (pin "P$2") (pinfunction "VPCC_P$2") (pintype "input"))
      (node (ref "R23") (pin "1") (pinfunction "1_1") (pintype "passive"))
      (node (ref "R24") (pin "1") (pinfunction "1_1") (pintype "passive"))
    )
    (net (code "56") (name "Net-(IC4-{slash}PG)") (class "Default")
      (node (ref "IC4") (pin "P$6") (pinfunction "/PG_P$6") (pintype "output"))
      (node (ref "PWR") (pin "C") (pinfunction "C_C") (pintype "passive"))
    )
    (net (code "57") (name "Net-(IC7A-+IN)") (class "Default")
      (node (ref "IC7") (pin "3") (pinfunction "+IN_3") (pintype "input"))
      (node (ref "J5") (pin "1") (pinfunction "1_1") (pintype "passive"))
    )
    (net (code "58") (name "Net-(IC7A--IN)") (class "Default")
      (node (ref "IC7") (pin "2") (pinfunction "-IN_2") (pintype "input"))
      (node (ref "R31") (pin "2") (pinfunction "2_2") (pintype "passive"))
      (node (ref "R32") (pin "1") (pinfunction "1_1") (pintype "passive"))
    )
    (net (code "59") (name "Net-(IC7B-+IN)") (class "Default")
      (node (ref "IC7") (pin "5") (pinfunction "+IN_5") (pintype "input"))
      (node (ref "J4") (pin "1") (pinfunction "1_1") (pintype "passive"))
    )
    (net (code "60") (name "Net-(IC7B--IN)") (class "Default")
      (node (ref "IC7") (pin "6") (pinfunction "-IN_6") (pintype "input"))
      (node (ref "R33") (pin "2") (pinfunction "2_2") (pintype "passive"))
      (node (ref "R34") (pin "1") (pinfunction "1_1") (pintype "passive"))
    )
    (net (code "61") (name "Net-(IC7C-+IN)") (class "Default")
      (node (ref "IC7") (pin "10") (pinfunction "+IN_10") (pintype "input"))
      (node (ref "J3") (pin "1") (pinfunction "1_1") (pintype "passive"))
    )
    (net (code "62") (name "Net-(IC7C--IN)") (class "Default")
      (node (ref "IC7") (pin "9") (pinfunction "-IN_9") (pintype "input"))
      (node (ref "R35") (pin "2") (pinfunction "2_2") (pintype "passive"))
      (node (ref "R36") (pin "1") (pinfunction "1_1") (pintype "passive"))
    )
    (net (code "63") (name "Net-(IC7D-+IN)") (class "Default")
      (node (ref "IC7") (pin "12") (pinfunction "+IN_12") (pintype "input"))
      (node (ref "J2") (pin "1") (pinfunction "1_1") (pintype "passive"))
    )
    (net (code "64") (name "Net-(IC7D--IN)") (class "Default")
      (node (ref "IC7") (pin "13") (pinfunction "-IN_13") (pintype "input"))
      (node (ref "R37") (pin "2") (pinfunction "2_2") (pintype "passive"))
      (node (ref "R38") (pin "1") (pinfunction "1_1") (pintype "passive"))
    )
    (net (code "65") (name "Net-(J1-GP4)") (class "Default")
      (node (ref "J1") (pin "7") (pinfunction "GP4_7") (pintype "bidirectional"))
      (node (ref "LED1") (pin "A") (pinfunction "A_A") (pintype "passive"))
    )
    (net (code "66") (name "Net-(L1-1)") (class "Default")
      (node (ref "L1") (pin "P$1") (pinfunction "1_P$1") (pintype "passive"))
      (node (ref "U2") (pin "3") (pinfunction "L_3") (pintype "passive"))
    )
    (net (code "67") (name "Net-(LED1-PadC)") (class "Default")
      (node (ref "LED1") (pin "C") (pinfunction "C_C") (pintype "passive"))
      (node (ref "R17") (pin "2") (pinfunction "2_2") (pintype "passive"))
    )
    (net (code "68") (name "Net-(PWR-PadA)") (class "Default")
      (node (ref "PWR") (pin "A") (pinfunction "A_A") (pintype "passive"))
      (node (ref "R27") (pin "1") (pinfunction "1_1") (pintype "passive"))
    )
    (net (code "69") (name "Net-(R30-Pad2)") (class "Default")
      (node (ref "R30") (pin "2") (pinfunction "2_2") (pintype "passive"))
      (node (ref "RT2") (pin "2") (pinfunction "2_2") (pintype "passive"))
      (node (ref "THERM") (pin "2") (pinfunction "2_2") (pintype "passive"))
    )
    (net (code "70") (name "Net-(U$2-X1)") (class "Default")
      (node (ref "R10") (pin "1") (pinfunction "1_1") (pintype "passive"))
      (node (ref "U$2") (pin "1") (pinfunction "X1_1") (pintype "bidirectional"))
      (node (ref "X1") (pin "2") (pinfunction "2_2") (pintype "passive"))
    )
    (net (code "71") (name "Net-(U$2-X2)") (class "Default")
      (node (ref "U$2") (pin "2") (pinfunction "X2_2") (pintype "bidirectional"))
      (node (ref "X1") (pin "1") (pinfunction "1_1") (pintype "passive"))
    )
    (net (code "72") (name "Net-(U1-DQ)") (class "Default")
      (node (ref "R9") (pin "2") (pinfunction "2_2") (pintype "passive"))
      (node (ref "U1") (pin "2") (pinfunction "DQ_2") (pintype "bidirectional"))
    )
    (net (code "73") (name "Net-(U2-FB)") (class "Default")
      (node (ref "R21") (pin "2") (pinfunction "2_2") (pintype "passive"))
      (node (ref "SJ1") (pin "2") (pinfunction "2_2") (pintype "passive"))
      (node (ref "U2") (pin "10") (pinfunction "FB_10") (pintype "passive"))
    )
    (net (code "74") (name "Net-(U2-UVLO)") (class "Default")
      (node (ref "C4") (pin "2") (pinfunction "2_2") (pintype "passive"))
      (node (ref "R18") (pin "1") (pinfunction "1_1") (pintype "passive"))
      (node (ref "R19") (pin "2") (pinfunction "2_2") (pintype "passive"))
      (node (ref "U2") (pin "7") (pinfunction "UVLO_7") (pintype "passive"))
    )
    (net (code "75") (name "Net-(U2-VAUX)") (class "Default")
      (node (ref "C5") (pin "1") (pinfunction "1_1") (pintype "passive"))
      (node (ref "U2") (pin "1") (pinfunction "VAUX_1") (pintype "passive"))
    )
    (net (code "76") (name "VCC") (class "Default")
      (node (ref "C10") (pin "+") (pinfunction "+_+") (pintype "passive"))
      (node (ref "C9") (pin "1") (pinfunction "1_1") (pintype "passive"))
      (node (ref "D2") (pin "C") (pinfunction "C_C") (pintype "passive"))
      (node (ref "IC4") (pin "P$17") (pinfunction "CE_P$17") (pintype "input"))
      (node (ref "IC4") (pin "P$18") (pinfunction "IN1_P$18") (pintype "input"))
      (node (ref "IC4") (pin "P$19") (pinfunction "IN2_P$19") (pintype "input"))
      (node (ref "IC4") (pin "P$3") (pinfunction "SEL_P$3") (pintype "input"))
      (node (ref "IC4") (pin "P$4") (pinfunction "PROG2_P$4") (pintype "input"))
      (node (ref "IC4") (pin "P$9") (pinfunction "/TE_P$9") (pintype "input"))
      (node (ref "R23") (pin "2") (pinfunction "2_2") (pintype "passive"))
      (node (ref "R25") (pin "2") (pinfunction "2_2") (pintype "passive"))
      (node (ref "R26") (pin "2") (pinfunction "2_2") (pintype "passive"))
      (node (ref "R27") (pin "2") (pinfunction "2_2") (pintype "passive"))
    )
    (net (code "77") (name "unconnected-(J1-CE1-Pad26)") (class "Default")
      (node (ref "J1") (pin "26") (pinfunction "CE1_26") (pintype "output"))
    )
    (net (code "78") (name "unconnected-(J1-GP16-Pad36)") (class "Default")
      (node (ref "J1") (pin "36") (pinfunction "GP16_36") (pintype "bidirectional"))
    )
    (net (code "79") (name "unconnected-(J1-GP17-Pad11)") (class "Default")
      (node (ref "J1") (pin "11") (pinfunction "GP17_11") (pintype "bidirectional"))
    )
    (net (code "80") (name "unconnected-(J1-GP18#-Pad12)") (class "Default")
      (node (ref "J1") (pin "12") (pinfunction "GP18#_12") (pintype "bidirectional"))
    )
    (net (code "81") (name "unconnected-(J1-GP19-Pad35)") (class "Default")
      (node (ref "J1") (pin "35") (pinfunction "GP19_35") (pintype "bidirectional"))
    )
    (net (code "82") (name "unconnected-(J1-GP20-Pad38)") (class "Default")
      (node (ref "J1") (pin "38") (pinfunction "GP20_38") (pintype "bidirectional"))
    )
    (net (code "83") (name "unconnected-(J1-GP21-Pad40)") (class "Default")
      (node (ref "J1") (pin "40") (pinfunction "GP21_40") (pintype "bidirectional"))
    )
    (net (code "84") (name "unconnected-(J1-GP23-Pad16)") (class "Default")
      (node (ref "J1") (pin "16") (pinfunction "GP23_16") (pintype "bidirectional"))
    )
    (net (code "85") (name "unconnected-(J1-GP24-Pad18)") (class "Default")
      (node (ref "J1") (pin "18") (pinfunction "GP24_18") (pintype "bidirectional"))
    )
    (net (code "86") (name "unconnected-(J1-GP25-Pad22)") (class "Default")
      (node (ref "J1") (pin "22") (pinfunction "GP25_22") (pintype "bidirectional"))
    )
    (net (code "87") (name "unconnected-(J1-GP26-Pad37)") (class "Default")
      (node (ref "J1") (pin "37") (pinfunction "GP26_37") (pintype "bidirectional"))
    )
    (net (code "88") (name "unconnected-(J1-ID_SC-Pad28)") (class "Default")
      (node (ref "J1") (pin "28") (pinfunction "ID_SC_28") (pintype "bidirectional"))
    )
    (net (code "89") (name "unconnected-(J1-ID_SD-Pad27)") (class "Default")
      (node (ref "J1") (pin "27") (pinfunction "ID_SD_27") (pintype "bidirectional"))
    )
    (net (code "90") (name "unconnected-(J1-SCL-Pad5)") (class "Default")
      (node (ref "J1") (pin "5") (pinfunction "SCL_5") (pintype "bidirectional"))
    )
    (net (code "91") (name "unconnected-(J1-SDA-Pad3)") (class "Default")
      (node (ref "J1") (pin "3") (pinfunction "SDA_3") (pintype "bidirectional"))
    )
    (net (code "92") (name "unconnected-(J2-Pad3)") (class "Default")
      (node (ref "J2") (pin "3") (pinfunction "3_3") (pintype "passive"))
    )
    (net (code "93") (name "unconnected-(J2-Pad4)") (class "Default")
      (node (ref "J2") (pin "4") (pinfunction "4_4") (pintype "passive"))
    )
    (net (code "94") (name "unconnected-(J3-Pad3)") (class "Default")
      (node (ref "J3") (pin "3") (pinfunction "3_3") (pintype "passive"))
    )
    (net (code "95") (name "unconnected-(J3-Pad4)") (class "Default")
      (node (ref "J3") (pin "4") (pinfunction "4_4") (pintype "passive"))
    )
    (net (code "96") (name "unconnected-(J4-Pad3)") (class "Default")
      (node (ref "J4") (pin "3") (pinfunction "3_3") (pintype "passive"))
    )
    (net (code "97") (name "unconnected-(J4-Pad4)") (class "Default")
      (node (ref "J4") (pin "4") (pinfunction "4_4") (pintype "passive"))
    )
    (net (code "98") (name "unconnected-(J5-Pad3)") (class "Default")
      (node (ref "J5") (pin "3") (pinfunction "3_3") (pintype "passive"))
    )
    (net (code "99") (name "unconnected-(J5-Pad4)") (class "Default")
      (node (ref "J5") (pin "4") (pinfunction "4_4") (pintype "passive"))
    )
    (net (code "100") (name "unconnected-(JP2-Pad4)") (class "Default")
      (node (ref "JP2") (pin "4") (pinfunction "4_4") (pintype "passive"))
    )
    (net (code "101") (name "unconnected-(JP2-Pad6)") (class "Default")
      (node (ref "JP2") (pin "6") (pinfunction "6_6") (pintype "passive"))
    )
    (net (code "102") (name "unconnected-(M1-IRQ-Pad8)") (class "Default")
      (node (ref "M1") (pin "8") (pinfunction "IRQ_8") (pintype "bidirectional"))
    )
  )
)
